# ESP32.net
KiCad netlist of a schematic drawn in Altium Designer
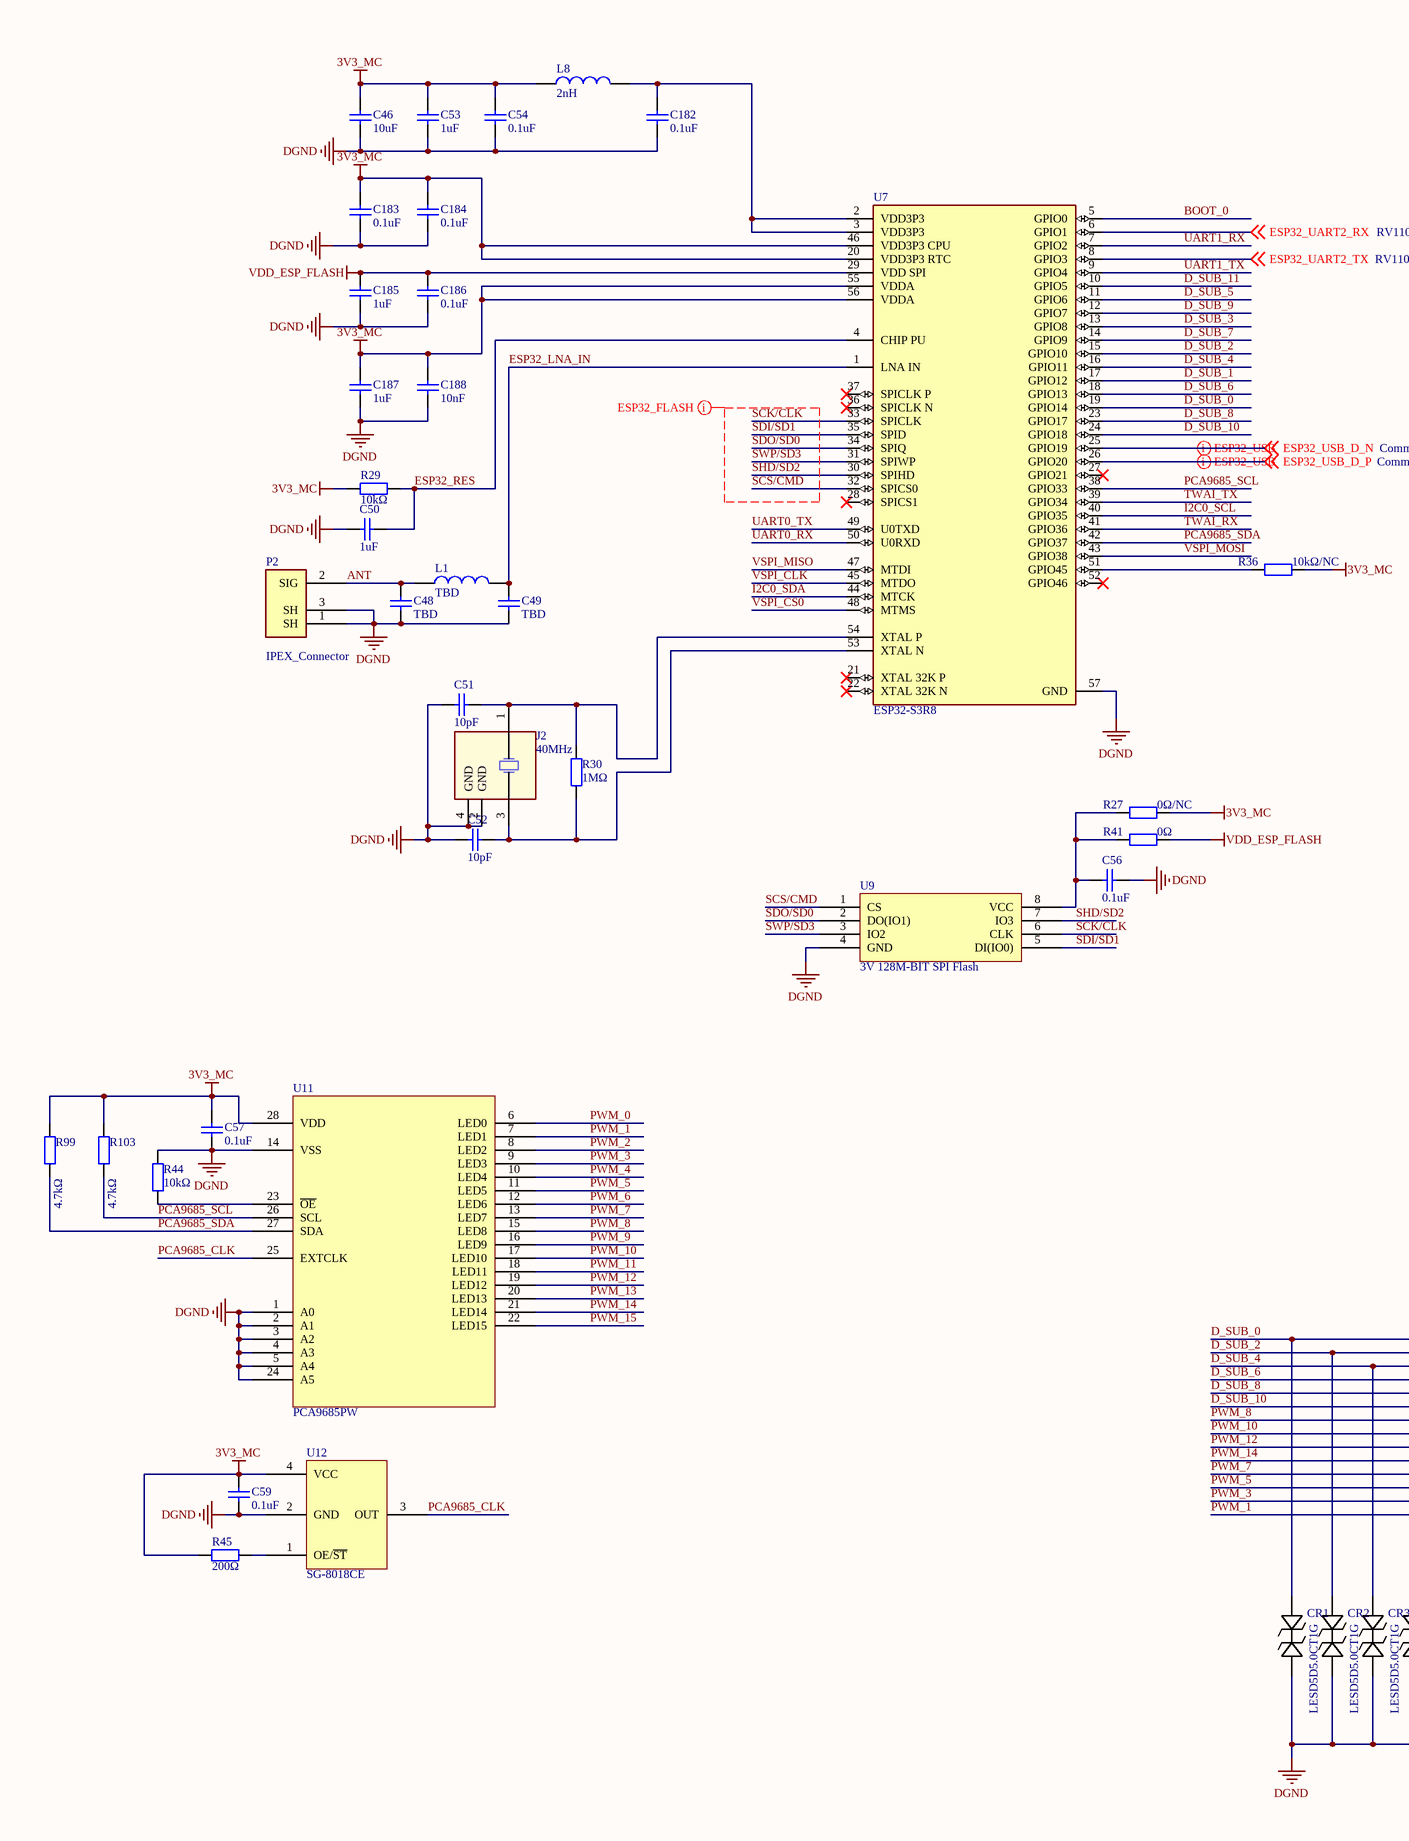
[diagram p0: ESP32.SchDoc, left]
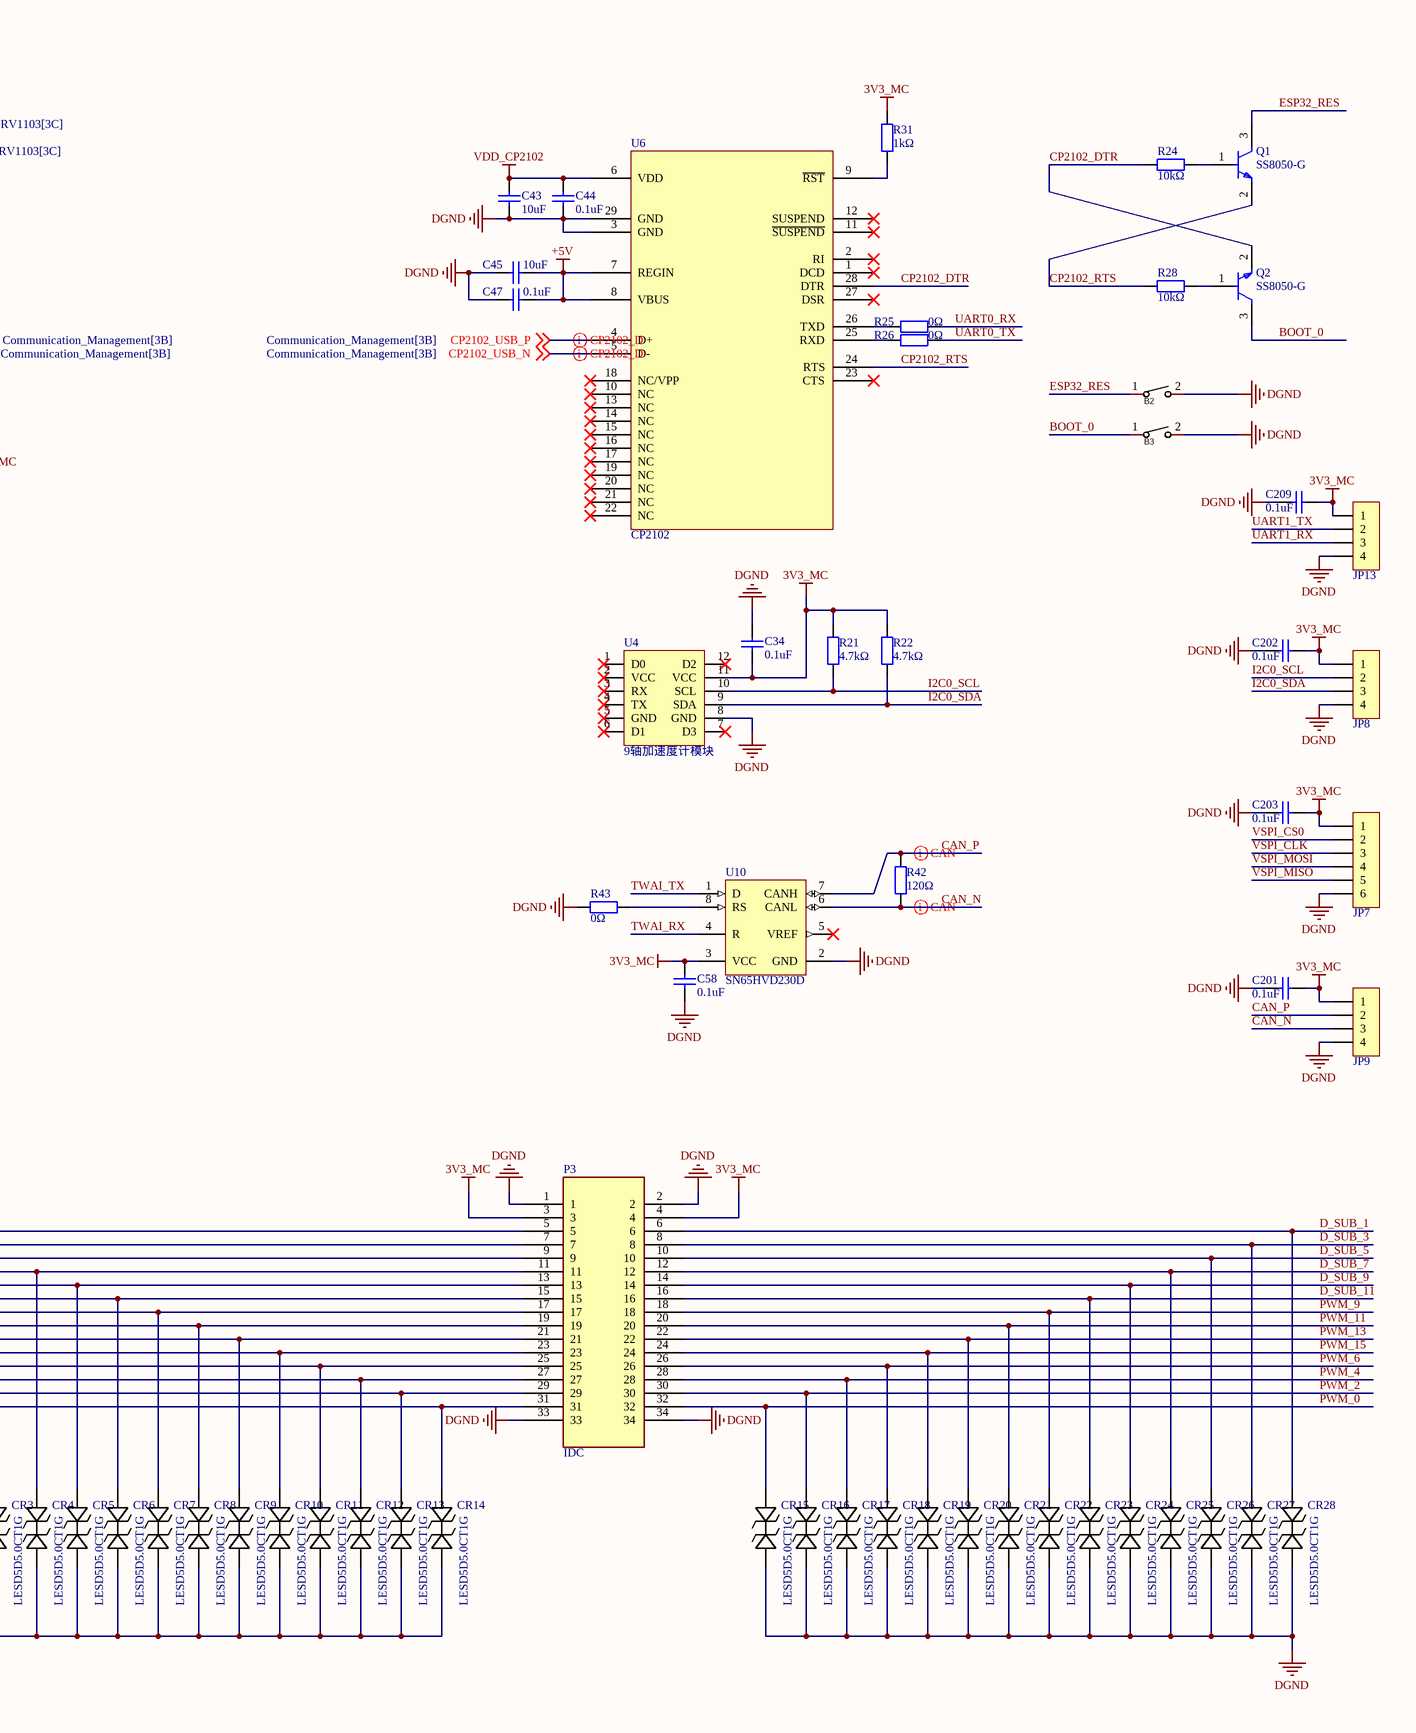
[diagram p1: ESP32.SchDoc, right]

(export (version "E")
  (design (tool "Eeschema 10.0.6"))
  (components
    (comp (ref "B2")
      (value "Bottom-2P-1Way")
      (footprint "SFerret:SW-SMD_L4.0-W2.9-LS5.0")
      (description "轻触按键")
      (fields (field (name "MANUFACTURER") "SHOU HAN(首韩)") (field (name "MANUFACTURER PART") "TS342A2P-WZ"))
      (libsource (lib "SFerret") (part "Bottom-2P-1Way"))
    )
    (comp (ref "B3")
      (value "Bottom-2P-1Way")
      (footprint "SW-SMD_L4.0-W2.9-LS5.0")
      (description "轻触按键")
      (fields (field (name "MANUFACTURER") "SHOU HAN(首韩)") (field (name "MANUFACTURER PART") "TS342A2P-WZ"))
      (libsource (lib "SFerret") (part "Bottom-2P-1Way"))
    )
    (comp (ref "C34")
      (value "0.1uF")
      (footprint "0603_C")
      (description "贴片电容")
      (libsource (lib "SFerret") (part "SMT_Cap"))
    )
    (comp (ref "C43")
      (value "10uF")
      (footprint "0603_C")
      (description "贴片电容")
      (libsource (lib "SFerret") (part "SMT_Cap"))
    )
    (comp (ref "C44")
      (value "0.1uF")
      (footprint "0603_C")
      (description "贴片电容")
      (libsource (lib "SFerret") (part "SMT_Cap"))
    )
    (comp (ref "C45")
      (value "10uF")
      (footprint "0603_C")
      (description "贴片电容")
      (libsource (lib "SFerret") (part "SMT_Cap"))
    )
    (comp (ref "C46")
      (value "10uF")
      (footprint "0603_C")
      (description "贴片电容")
      (libsource (lib "SFerret") (part "SMT_Cap"))
    )
    (comp (ref "C47")
      (value "0.1uF")
      (footprint "0603_C")
      (description "贴片电容")
      (libsource (lib "SFerret") (part "SMT_Cap"))
    )
    (comp (ref "C48")
      (value "TBD")
      (footprint "0402_C")
      (description "贴片电容")
      (libsource (lib "SFerret") (part "SMT_Cap"))
    )
    (comp (ref "C49")
      (value "TBD")
      (footprint "0402_C")
      (description "贴片电容")
      (libsource (lib "SFerret") (part "SMT_Cap"))
    )
    (comp (ref "C50")
      (value "1uF")
      (footprint "0402_C")
      (description "贴片电容")
      (libsource (lib "SFerret") (part "SMT_Cap"))
    )
    (comp (ref "C51")
      (value "10pF")
      (footprint "0402_C")
      (description "贴片电容")
      (libsource (lib "SFerret") (part "SMT_Cap"))
    )
    (comp (ref "C52")
      (value "10pF")
      (footprint "0402_C")
      (description "贴片电容")
      (libsource (lib "SFerret") (part "SMT_Cap"))
    )
    (comp (ref "C53")
      (value "1uF")
      (footprint "0603_C")
      (description "贴片电容")
      (libsource (lib "SFerret") (part "SMT_Cap"))
    )
    (comp (ref "C54")
      (value "0.1uF")
      (footprint "0402_C")
      (description "贴片电容")
      (libsource (lib "SFerret") (part "SMT_Cap"))
    )
    (comp (ref "C56")
      (value "0.1uF")
      (footprint "0603_C")
      (description "贴片电容")
      (libsource (lib "SFerret") (part "SMT_Cap"))
    )
    (comp (ref "C57")
      (value "0.1uF")
      (footprint "0603_C")
      (description "贴片电容")
      (libsource (lib "SFerret") (part "SMT_Cap"))
    )
    (comp (ref "C58")
      (value "0.1uF")
      (footprint "0603_C")
      (description "贴片电容")
      (libsource (lib "SFerret") (part "SMT_Cap"))
    )
    (comp (ref "C59")
      (value "0.1uF")
      (footprint "0603_C")
      (description "贴片电容")
      (libsource (lib "SFerret") (part "SMT_Cap"))
    )
    (comp (ref "C182")
      (value "0.1uF")
      (footprint "0402_C")
      (description "贴片电容")
      (libsource (lib "SFerret") (part "SMT_Cap"))
    )
    (comp (ref "C183")
      (value "0.1uF")
      (footprint "0402_C")
      (description "贴片电容")
      (libsource (lib "SFerret") (part "SMT_Cap"))
    )
    (comp (ref "C184")
      (value "0.1uF")
      (footprint "0402_C")
      (description "贴片电容")
      (libsource (lib "SFerret") (part "SMT_Cap"))
    )
    (comp (ref "C185")
      (value "1uF")
      (footprint "0402_C")
      (description "贴片电容")
      (libsource (lib "SFerret") (part "SMT_Cap"))
    )
    (comp (ref "C186")
      (value "0.1uF")
      (footprint "0402_C")
      (description "贴片电容")
      (libsource (lib "SFerret") (part "SMT_Cap"))
    )
    (comp (ref "C187")
      (value "1uF")
      (footprint "0402_C")
      (description "贴片电容")
      (libsource (lib "SFerret") (part "SMT_Cap"))
    )
    (comp (ref "C188")
      (value "10nF")
      (footprint "0402_C")
      (description "贴片电容")
      (libsource (lib "SFerret") (part "SMT_Cap"))
    )
    (comp (ref "C201")
      (value "0.1uF")
      (footprint "0603_C")
      (description "贴片电容")
      (libsource (lib "SFerret") (part "SMT_Cap"))
    )
    (comp (ref "C202")
      (value "0.1uF")
      (footprint "0603_C")
      (description "贴片电容")
      (libsource (lib "SFerret") (part "SMT_Cap"))
    )
    (comp (ref "C203")
      (value "0.1uF")
      (footprint "0603_C")
      (description "贴片电容")
      (libsource (lib "SFerret") (part "SMT_Cap"))
    )
    (comp (ref "C209")
      (value "0.1uF")
      (footprint "0603_C")
      (description "贴片电容")
      (libsource (lib "SFerret") (part "SMT_Cap"))
    )
    (comp (ref "CR1")
      (value "LESD5D5.0CT1G")
      (footprint "CR_5.0CT1G_UMW")
      (description "TVS")
      (libsource (lib "SFerret") (part "LESD5D5.0CT1G"))
    )
    (comp (ref "CR2")
      (value "LESD5D5.0CT1G")
      (footprint "CR_5.0CT1G_UMW")
      (description "TVS")
      (libsource (lib "SFerret") (part "LESD5D5.0CT1G"))
    )
    (comp (ref "CR3")
      (value "LESD5D5.0CT1G")
      (footprint "CR_5.0CT1G_UMW")
      (description "TVS")
      (libsource (lib "SFerret") (part "LESD5D5.0CT1G"))
    )
    (comp (ref "CR4")
      (value "LESD5D5.0CT1G")
      (footprint "CR_5.0CT1G_UMW")
      (description "TVS")
      (libsource (lib "SFerret") (part "LESD5D5.0CT1G"))
    )
    (comp (ref "CR5")
      (value "LESD5D5.0CT1G")
      (footprint "CR_5.0CT1G_UMW")
      (description "TVS")
      (libsource (lib "SFerret") (part "LESD5D5.0CT1G"))
    )
    (comp (ref "CR6")
      (value "LESD5D5.0CT1G")
      (footprint "CR_5.0CT1G_UMW")
      (description "TVS")
      (libsource (lib "SFerret") (part "LESD5D5.0CT1G"))
    )
    (comp (ref "CR7")
      (value "LESD5D5.0CT1G")
      (footprint "CR_5.0CT1G_UMW")
      (description "TVS")
      (libsource (lib "SFerret") (part "LESD5D5.0CT1G"))
    )
    (comp (ref "CR8")
      (value "LESD5D5.0CT1G")
      (footprint "CR_5.0CT1G_UMW")
      (description "TVS")
      (libsource (lib "SFerret") (part "LESD5D5.0CT1G"))
    )
    (comp (ref "CR9")
      (value "LESD5D5.0CT1G")
      (footprint "CR_5.0CT1G_UMW")
      (description "TVS")
      (libsource (lib "SFerret") (part "LESD5D5.0CT1G"))
    )
    (comp (ref "CR10")
      (value "LESD5D5.0CT1G")
      (footprint "CR_5.0CT1G_UMW")
      (description "TVS")
      (libsource (lib "SFerret") (part "LESD5D5.0CT1G"))
    )
    (comp (ref "CR11")
      (value "LESD5D5.0CT1G")
      (footprint "CR_5.0CT1G_UMW")
      (description "TVS")
      (libsource (lib "SFerret") (part "LESD5D5.0CT1G"))
    )
    (comp (ref "CR12")
      (value "LESD5D5.0CT1G")
      (footprint "CR_5.0CT1G_UMW")
      (description "TVS")
      (libsource (lib "SFerret") (part "LESD5D5.0CT1G"))
    )
    (comp (ref "CR13")
      (value "LESD5D5.0CT1G")
      (footprint "CR_5.0CT1G_UMW")
      (description "TVS")
      (libsource (lib "SFerret") (part "LESD5D5.0CT1G"))
    )
    (comp (ref "CR14")
      (value "LESD5D5.0CT1G")
      (footprint "CR_5.0CT1G_UMW")
      (description "TVS")
      (libsource (lib "SFerret") (part "LESD5D5.0CT1G"))
    )
    (comp (ref "CR15")
      (value "LESD5D5.0CT1G")
      (footprint "CR_5.0CT1G_UMW")
      (description "TVS")
      (libsource (lib "SFerret") (part "LESD5D5.0CT1G"))
    )
    (comp (ref "CR16")
      (value "LESD5D5.0CT1G")
      (footprint "CR_5.0CT1G_UMW")
      (description "TVS")
      (libsource (lib "SFerret") (part "LESD5D5.0CT1G"))
    )
    (comp (ref "CR17")
      (value "LESD5D5.0CT1G")
      (footprint "CR_5.0CT1G_UMW")
      (description "TVS")
      (libsource (lib "SFerret") (part "LESD5D5.0CT1G"))
    )
    (comp (ref "CR18")
      (value "LESD5D5.0CT1G")
      (footprint "CR_5.0CT1G_UMW")
      (description "TVS")
      (libsource (lib "SFerret") (part "LESD5D5.0CT1G"))
    )
    (comp (ref "CR19")
      (value "LESD5D5.0CT1G")
      (footprint "CR_5.0CT1G_UMW")
      (description "TVS")
      (libsource (lib "SFerret") (part "LESD5D5.0CT1G"))
    )
    (comp (ref "CR20")
      (value "LESD5D5.0CT1G")
      (footprint "CR_5.0CT1G_UMW")
      (description "TVS")
      (libsource (lib "SFerret") (part "LESD5D5.0CT1G"))
    )
    (comp (ref "CR21")
      (value "LESD5D5.0CT1G")
      (footprint "CR_5.0CT1G_UMW")
      (description "TVS")
      (libsource (lib "SFerret") (part "LESD5D5.0CT1G"))
    )
    (comp (ref "CR22")
      (value "LESD5D5.0CT1G")
      (footprint "CR_5.0CT1G_UMW")
      (description "TVS")
      (libsource (lib "SFerret") (part "LESD5D5.0CT1G"))
    )
    (comp (ref "CR23")
      (value "LESD5D5.0CT1G")
      (footprint "CR_5.0CT1G_UMW")
      (description "TVS")
      (libsource (lib "SFerret") (part "LESD5D5.0CT1G"))
    )
    (comp (ref "CR24")
      (value "LESD5D5.0CT1G")
      (footprint "CR_5.0CT1G_UMW")
      (description "TVS")
      (libsource (lib "SFerret") (part "LESD5D5.0CT1G"))
    )
    (comp (ref "CR25")
      (value "LESD5D5.0CT1G")
      (footprint "CR_5.0CT1G_UMW")
      (description "TVS")
      (libsource (lib "SFerret") (part "LESD5D5.0CT1G"))
    )
    (comp (ref "CR26")
      (value "LESD5D5.0CT1G")
      (footprint "CR_5.0CT1G_UMW")
      (description "TVS")
      (libsource (lib "SFerret") (part "LESD5D5.0CT1G"))
    )
    (comp (ref "CR27")
      (value "LESD5D5.0CT1G")
      (footprint "CR_5.0CT1G_UMW")
      (description "TVS")
      (libsource (lib "SFerret") (part "LESD5D5.0CT1G"))
    )
    (comp (ref "CR28")
      (value "LESD5D5.0CT1G")
      (footprint "CR_5.0CT1G_UMW")
      (description "TVS")
      (libsource (lib "SFerret") (part "LESD5D5.0CT1G"))
    )
    (comp (ref "J2")
      (value "40MHz")
      (footprint "SMD-2520_4P")
      (libsource (lib "SFerret") (part "Oscillator_SMT_4P"))
    )
    (comp (ref "JP7")
      (value "HDR-1X6")
      (footprint "MX 1.25-LS-6P")
      (description "6P接插件")
      (libsource (lib "5.0 - 接插件-脚距1.25") (part "Header 6"))
    )
    (comp (ref "JP8")
      (value "HDR-1X4")
      (footprint "MX 1.25-LS-4P")
      (description "4P接插件")
      (libsource (lib "5.0 - 接插件-脚距1.25") (part "Header 4"))
    )
    (comp (ref "JP9")
      (value "HDR-1X4")
      (footprint "MX 1.25-LS-4P")
      (description "4P接插件")
      (libsource (lib "5.0 - 接插件-脚距1.25") (part "Header 4"))
    )
    (comp (ref "JP13")
      (value "HDR-1X4")
      (footprint "MX 1.25-LS-4P")
      (description "4P接插件")
      (libsource (lib "5.0 - 接插件-脚距1.25") (part "Header 4"))
    )
    (comp (ref "L1")
      (value "TBD")
      (footprint "0402_L")
      (description "贴片电感")
      (libsource (lib "SFerret") (part "SMT_Iud"))
    )
    (comp (ref "L8")
      (value "2nH")
      (footprint "0402_L")
      (description "贴片电感")
      (libsource (lib "SFerret") (part "SMT_Iud"))
    )
    (comp (ref "P2")
      (value "IPEX_Connector")
      (footprint "IPEX")
      (libsource (lib "SFerret") (part "IPEX_Connector"))
    )
    (comp (ref "P3")
      (value "IDC")
      (footprint "IDC2.54-LI-2x17P")
      (libsource (lib "SFerret") (part "IDC 2x17P"))
    )
    (comp (ref "Q1")
      (value "SS8050-G")
      (footprint "FP-SS8050-G-MFG")
      (description "NPN TRANSISTOR 1.5A 40V SOT-23 R")
      (libsource (lib "Altium Content Vault") (part "2a1388f82443b098dcd57d24ac7632d"))
    )
    (comp (ref "Q2")
      (value "SS8050-G")
      (footprint "FP-SS8050-G-MFG")
      (description "NPN TRANSISTOR 1.5A 40V SOT-23 R")
      (libsource (lib "Altium Content Vault") (part "2a1388f82443b098dcd57d24ac7632d"))
    )
    (comp (ref "R21")
      (value "4.7kΩ")
      (footprint "0603_R")
      (description "贴片电阻")
      (libsource (lib "") (part "SMT_Res_1"))
    )
    (comp (ref "R22")
      (value "4.7kΩ")
      (footprint "0603_R")
      (description "贴片电阻")
      (libsource (lib "") (part "SMT_Res_1"))
    )
    (comp (ref "R24")
      (value "10kΩ")
      (footprint "0603_R")
      (description "贴片电阻")
      (libsource (lib "") (part "SMT_Res_3"))
    )
    (comp (ref "R25")
      (value "0Ω")
      (footprint "0603_R")
      (description "贴片电阻")
      (libsource (lib "") (part "SMT_Res_3"))
    )
    (comp (ref "R26")
      (value "0Ω")
      (footprint "0603_R")
      (description "贴片电阻")
      (libsource (lib "") (part "SMT_Res_3"))
    )
    (comp (ref "R27")
      (value "0Ω/NC")
      (footprint "0402_R")
      (description "贴片电阻")
      (libsource (lib "") (part "SMT_Res_3"))
    )
    (comp (ref "R28")
      (value "10kΩ")
      (footprint "0603_R")
      (description "贴片电阻")
      (libsource (lib "") (part "SMT_Res_3"))
    )
    (comp (ref "R29")
      (value "10kΩ")
      (footprint "0402_R")
      (description "贴片电阻")
      (libsource (lib "") (part "SMT_Res_3"))
    )
    (comp (ref "R30")
      (value "1MΩ")
      (footprint "0402_R")
      (description "贴片电阻")
      (libsource (lib "SFerret") (part "SMT_Res"))
    )
    (comp (ref "R31")
      (value "1kΩ")
      (footprint "0603_R")
      (description "贴片电阻")
      (libsource (lib "") (part "SMT_Res_1"))
    )
    (comp (ref "R36")
      (value "10kΩ/NC")
      (footprint "0402_R")
      (description "贴片电阻")
      (libsource (lib "") (part "SMT_Res_3"))
    )
    (comp (ref "R41")
      (value "0Ω")
      (footprint "0402_R")
      (description "贴片电阻")
      (libsource (lib "") (part "SMT_Res_3"))
    )
    (comp (ref "R42")
      (value "120Ω")
      (footprint "0805_R")
      (description "贴片电阻")
      (libsource (lib "") (part "SMT_Res_1"))
    )
    (comp (ref "R43")
      (value "0Ω")
      (footprint "0603_R")
      (description "贴片电阻")
      (libsource (lib "") (part "SMT_Res_3"))
    )
    (comp (ref "R44")
      (value "10kΩ")
      (footprint "0603_R")
      (description "贴片电阻")
      (libsource (lib "") (part "SMT_Res_1"))
    )
    (comp (ref "R45")
      (value "200Ω")
      (footprint "0603_R")
      (description "贴片电阻")
      (libsource (lib "") (part "SMT_Res_2"))
    )
    (comp (ref "R99")
      (value "4.7kΩ")
      (footprint "0603_R")
      (description "贴片电阻")
      (libsource (lib "SFerret") (part "SMT_Res"))
    )
    (comp (ref "R103")
      (value "4.7kΩ")
      (footprint "0603_R")
      (description "贴片电阻")
      (libsource (lib "SFerret") (part "SMT_Res"))
    )
    (comp (ref "U4") (value "9轴加速度计模块") (footprint "9轴加速度计") (libsource (lib "集大电协1.5") (part "9轴加速度计")))
    (comp (ref "U6")
      (value "CP2102")
      (footprint "QFN50P500X500X100_HS-29N")
      (description "SINGLE-CHIP USB TO UART BRIDGE")
      (libsource (lib "SFerret") (part "CP2102"))
    )
    (comp (ref "U7")
      (value "ESP32-S3R8")
      (footprint "QFN40P700X700X90_HS-57M")
      (description "ESP32-S3R8 RF System")
      (libsource (lib "SFerret") (part "ESP32-S3R8"))
    )
    (comp (ref "U9")
      (value "3V 128M-BIT SPI Flash")
      (footprint "SOIC-8-Body 5.28x5.28mm")
      (libsource (lib "SFerret") (part "W25Q128JVPIQ"))
    )
    (comp (ref "U10")
      (value "SN65HVD230D")
      (footprint "D0008A_M")
      (description "CAN Bus Transceiver, 3.3 V, -40 to 85 degC, 8-Pin SOIC (D), Green (RoHS & no Sb/Br), Tube")
      (fields (field (name "GENERIC PART NUMBER") "SN65HVD230"))
      (libsource (lib "Altium Content Vault") (part "TI-SN65HVD230D-SOIC_D-8"))
    )
    (comp (ref "U11")
      (value "PCA9685PW")
      (footprint "SOP65P640X110-28N")
      (description "16-Channel, 12-bit PWM Fm+ I²C-Bus LED Driver")
      (libsource (lib "SFerret") (part "PCA9685PW"))
    )
    (comp (ref "U12")
      (value "SG-8018CE")
      (footprint "OSC-2520-4P")
      (description "CRYSTAL OSCILLATOR (Programmable)")
      (libsource (lib "SFerret") (part "SG-8018CG_50Mhz"))
    )
  )
  (nets
    (net (code "1") (name "+5V") (class "Default")
      (node (ref "C45") (pin "1") (pinfunction "1_1") (pintype "passive"))
      (node (ref "C47") (pin "1") (pinfunction "1_1") (pintype "passive"))
      (node (ref "U6") (pin "7") (pinfunction "REGIN_7") (pintype "passive"))
      (node (ref "U6") (pin "8") (pinfunction "VBUS_8") (pintype "passive"))
    )
    (net (code "2") (name "/ANT") (class "Default")
      (node (ref "C48") (pin "2") (pinfunction "2_2") (pintype "passive"))
      (node (ref "L1") (pin "1") (pinfunction "1_1") (pintype "passive"))
      (node (ref "P2") (pin "2") (pinfunction "SIG_2") (pintype "passive"))
    )
    (net (code "3") (name "/BOOT_0") (class "Default")
      (node (ref "B3") (pin "1") (pinfunction "1_1") (pintype "passive"))
      (node (ref "Q2") (pin "3") (pinfunction "C_3") (pintype "passive"))
      (node (ref "U7") (pin "5") (pinfunction "GPIO0_5") (pintype "bidirectional"))
    )
    (net (code "4") (name "/CAN_N") (class "Default")
      (node (ref "JP9") (pin "3") (pinfunction "3_3") (pintype "passive"))
      (node (ref "R42") (pin "1") (pinfunction "1_1") (pintype "passive"))
      (node (ref "U10") (pin "6") (pinfunction "CANL_6") (pintype "bidirectional"))
    )
    (net (code "5") (name "/CAN_P") (class "Default")
      (node (ref "JP9") (pin "2") (pinfunction "2_2") (pintype "passive"))
      (node (ref "R42") (pin "2") (pinfunction "2_2") (pintype "passive"))
      (node (ref "U10") (pin "7") (pinfunction "CANH_7") (pintype "bidirectional"))
    )
    (net (code "6") (name "/CP2102_DTR") (class "Default")
      (node (ref "Q2") (pin "2") (pinfunction "E_2") (pintype "passive"))
      (node (ref "R24") (pin "1") (pinfunction "1_1") (pintype "passive"))
      (node (ref "U6") (pin "28") (pinfunction "DTR_28") (pintype "passive"))
    )
    (net (code "7") (name "/CP2102_RTS") (class "Default")
      (node (ref "Q1") (pin "2") (pinfunction "E_2") (pintype "passive"))
      (node (ref "R28") (pin "1") (pinfunction "1_1") (pintype "passive"))
      (node (ref "U6") (pin "24") (pinfunction "RTS_24") (pintype "passive"))
    )
    (net (code "8") (name "/D_SUB_0") (class "Default")
      (node (ref "CR1") (pin "1") (pinfunction "1_1") (pintype "passive"))
      (node (ref "P3") (pin "5") (pinfunction "5_5") (pintype "passive"))
      (node (ref "U7") (pin "19") (pinfunction "GPIO14_19") (pintype "bidirectional"))
    )
    (net (code "9") (name "/D_SUB_1") (class "Default")
      (node (ref "CR28") (pin "1") (pinfunction "1_1") (pintype "passive"))
      (node (ref "P3") (pin "6") (pinfunction "6_6") (pintype "passive"))
      (node (ref "U7") (pin "17") (pinfunction "GPIO12_17") (pintype "bidirectional"))
    )
    (net (code "10") (name "/D_SUB_2") (class "Default")
      (node (ref "CR2") (pin "1") (pinfunction "1_1") (pintype "passive"))
      (node (ref "P3") (pin "7") (pinfunction "7_7") (pintype "passive"))
      (node (ref "U7") (pin "15") (pinfunction "GPIO10_15") (pintype "bidirectional"))
    )
    (net (code "11") (name "/D_SUB_3") (class "Default")
      (node (ref "CR27") (pin "1") (pinfunction "1_1") (pintype "passive"))
      (node (ref "P3") (pin "8") (pinfunction "8_8") (pintype "passive"))
      (node (ref "U7") (pin "13") (pinfunction "GPIO8_13") (pintype "bidirectional"))
    )
    (net (code "12") (name "/D_SUB_4") (class "Default")
      (node (ref "CR3") (pin "1") (pinfunction "1_1") (pintype "passive"))
      (node (ref "P3") (pin "9") (pinfunction "9_9") (pintype "passive"))
      (node (ref "U7") (pin "16") (pinfunction "GPIO11_16") (pintype "bidirectional"))
    )
    (net (code "13") (name "/D_SUB_5") (class "Default")
      (node (ref "CR26") (pin "1") (pinfunction "1_1") (pintype "passive"))
      (node (ref "P3") (pin "10") (pinfunction "10_10") (pintype "passive"))
      (node (ref "U7") (pin "11") (pinfunction "GPIO6_11") (pintype "bidirectional"))
    )
    (net (code "14") (name "/D_SUB_6") (class "Default")
      (node (ref "CR4") (pin "1") (pinfunction "1_1") (pintype "passive"))
      (node (ref "P3") (pin "11") (pinfunction "11_11") (pintype "passive"))
      (node (ref "U7") (pin "18") (pinfunction "GPIO13_18") (pintype "bidirectional"))
    )
    (net (code "15") (name "/D_SUB_7") (class "Default")
      (node (ref "CR25") (pin "1") (pinfunction "1_1") (pintype "passive"))
      (node (ref "P3") (pin "12") (pinfunction "12_12") (pintype "passive"))
      (node (ref "U7") (pin "14") (pinfunction "GPIO9_14") (pintype "bidirectional"))
    )
    (net (code "16") (name "/D_SUB_8") (class "Default")
      (node (ref "CR5") (pin "1") (pinfunction "1_1") (pintype "passive"))
      (node (ref "P3") (pin "13") (pinfunction "13_13") (pintype "passive"))
      (node (ref "U7") (pin "23") (pinfunction "GPIO17_23") (pintype "bidirectional"))
    )
    (net (code "17") (name "/D_SUB_9") (class "Default")
      (node (ref "CR24") (pin "1") (pinfunction "1_1") (pintype "passive"))
      (node (ref "P3") (pin "14") (pinfunction "14_14") (pintype "passive"))
      (node (ref "U7") (pin "12") (pinfunction "GPIO7_12") (pintype "bidirectional"))
    )
    (net (code "18") (name "/D_SUB_10") (class "Default")
      (node (ref "CR6") (pin "1") (pinfunction "1_1") (pintype "passive"))
      (node (ref "P3") (pin "15") (pinfunction "15_15") (pintype "passive"))
      (node (ref "U7") (pin "24") (pinfunction "GPIO18_24") (pintype "bidirectional"))
    )
    (net (code "19") (name "/D_SUB_11") (class "Default")
      (node (ref "CR23") (pin "1") (pinfunction "1_1") (pintype "passive"))
      (node (ref "P3") (pin "16") (pinfunction "16_16") (pintype "passive"))
      (node (ref "U7") (pin "10") (pinfunction "GPIO5_10") (pintype "bidirectional"))
    )
    (net (code "20") (name "/ESP32_LNA_IN") (class "Default")
      (node (ref "C49") (pin "2") (pinfunction "2_2") (pintype "passive"))
      (node (ref "L1") (pin "2") (pinfunction "2_2") (pintype "passive"))
      (node (ref "U7") (pin "1") (pinfunction "LNA_IN_1") (pintype "passive"))
    )
    (net (code "21") (name "/ESP32_RES") (class "Default")
      (node (ref "B2") (pin "1") (pinfunction "1_1") (pintype "passive"))
      (node (ref "C50") (pin "2") (pinfunction "2_2") (pintype "passive"))
      (node (ref "Q1") (pin "3") (pinfunction "C_3") (pintype "passive"))
      (node (ref "R29") (pin "2") (pinfunction "2_2") (pintype "passive"))
      (node (ref "U7") (pin "4") (pinfunction "CHIP_PU_4") (pintype "passive"))
    )
    (net (code "22") (name "/I2C0_SCL") (class "Default")
      (node (ref "JP8") (pin "2") (pinfunction "2_2") (pintype "passive"))
      (node (ref "R21") (pin "1") (pinfunction "1_1") (pintype "passive"))
      (node (ref "U4") (pin "10") (pinfunction "SCL_10") (pintype "passive"))
      (node (ref "U7") (pin "40") (pinfunction "GPIO35_40") (pintype "bidirectional"))
    )
    (net (code "23") (name "/I2C0_SDA") (class "Default")
      (node (ref "JP8") (pin "3") (pinfunction "3_3") (pintype "passive"))
      (node (ref "R22") (pin "1") (pinfunction "1_1") (pintype "passive"))
      (node (ref "U4") (pin "9") (pinfunction "SDA_9") (pintype "passive"))
      (node (ref "U7") (pin "44") (pinfunction "MTCK_44") (pintype "bidirectional"))
    )
    (net (code "24") (name "/PCA9685_CLK") (class "Default")
      (node (ref "U11") (pin "25") (pinfunction "EXTCLK_25") (pintype "passive"))
      (node (ref "U12") (pin "3") (pinfunction "OUT_3") (pintype "passive"))
    )
    (net (code "25") (name "/PCA9685_SCL") (class "Default")
      (node (ref "R103") (pin "2") (pinfunction "2_2") (pintype "passive"))
      (node (ref "U11") (pin "26") (pinfunction "SCL_26") (pintype "passive"))
      (node (ref "U7") (pin "38") (pinfunction "GPIO33_38") (pintype "bidirectional"))
    )
    (net (code "26") (name "/PCA9685_SDA") (class "Default")
      (node (ref "R99") (pin "2") (pinfunction "2_2") (pintype "passive"))
      (node (ref "U11") (pin "27") (pinfunction "SDA_27") (pintype "passive"))
      (node (ref "U7") (pin "42") (pinfunction "GPIO37_42") (pintype "bidirectional"))
    )
    (net (code "27") (name "/PWM_0") (class "Default")
      (node (ref "CR15") (pin "1") (pinfunction "1_1") (pintype "passive"))
      (node (ref "P3") (pin "32") (pinfunction "32_32") (pintype "passive"))
      (node (ref "U11") (pin "6") (pinfunction "LED0_6") (pintype "passive"))
    )
    (net (code "28") (name "/PWM_1") (class "Default")
      (node (ref "CR14") (pin "1") (pinfunction "1_1") (pintype "passive"))
      (node (ref "P3") (pin "31") (pinfunction "31_31") (pintype "passive"))
      (node (ref "U11") (pin "7") (pinfunction "LED1_7") (pintype "passive"))
    )
    (net (code "29") (name "/PWM_2") (class "Default")
      (node (ref "CR16") (pin "1") (pinfunction "1_1") (pintype "passive"))
      (node (ref "P3") (pin "30") (pinfunction "30_30") (pintype "passive"))
      (node (ref "U11") (pin "8") (pinfunction "LED2_8") (pintype "passive"))
    )
    (net (code "30") (name "/PWM_3") (class "Default")
      (node (ref "CR13") (pin "1") (pinfunction "1_1") (pintype "passive"))
      (node (ref "P3") (pin "29") (pinfunction "29_29") (pintype "passive"))
      (node (ref "U11") (pin "9") (pinfunction "LED3_9") (pintype "passive"))
    )
    (net (code "31") (name "/PWM_4") (class "Default")
      (node (ref "CR17") (pin "1") (pinfunction "1_1") (pintype "passive"))
      (node (ref "P3") (pin "28") (pinfunction "28_28") (pintype "passive"))
      (node (ref "U11") (pin "10") (pinfunction "LED4_10") (pintype "passive"))
    )
    (net (code "32") (name "/PWM_5") (class "Default")
      (node (ref "CR12") (pin "1") (pinfunction "1_1") (pintype "passive"))
      (node (ref "P3") (pin "27") (pinfunction "27_27") (pintype "passive"))
      (node (ref "U11") (pin "11") (pinfunction "LED5_11") (pintype "passive"))
    )
    (net (code "33") (name "/PWM_6") (class "Default")
      (node (ref "CR18") (pin "1") (pinfunction "1_1") (pintype "passive"))
      (node (ref "P3") (pin "26") (pinfunction "26_26") (pintype "passive"))
      (node (ref "U11") (pin "12") (pinfunction "LED6_12") (pintype "passive"))
    )
    (net (code "34") (name "/PWM_7") (class "Default")
      (node (ref "CR11") (pin "1") (pinfunction "1_1") (pintype "passive"))
      (node (ref "P3") (pin "25") (pinfunction "25_25") (pintype "passive"))
      (node (ref "U11") (pin "13") (pinfunction "LED7_13") (pintype "passive"))
    )
    (net (code "35") (name "/PWM_8") (class "Default")
      (node (ref "CR7") (pin "1") (pinfunction "1_1") (pintype "passive"))
      (node (ref "P3") (pin "17") (pinfunction "17_17") (pintype "passive"))
      (node (ref "U11") (pin "15") (pinfunction "LED8_15") (pintype "passive"))
    )
    (net (code "36") (name "/PWM_9") (class "Default")
      (node (ref "CR22") (pin "1") (pinfunction "1_1") (pintype "passive"))
      (node (ref "P3") (pin "18") (pinfunction "18_18") (pintype "passive"))
      (node (ref "U11") (pin "16") (pinfunction "LED9_16") (pintype "passive"))
    )
    (net (code "37") (name "/PWM_10") (class "Default")
      (node (ref "CR8") (pin "1") (pinfunction "1_1") (pintype "passive"))
      (node (ref "P3") (pin "19") (pinfunction "19_19") (pintype "passive"))
      (node (ref "U11") (pin "17") (pinfunction "LED10_17") (pintype "passive"))
    )
    (net (code "38") (name "/PWM_11") (class "Default")
      (node (ref "CR21") (pin "1") (pinfunction "1_1") (pintype "passive"))
      (node (ref "P3") (pin "20") (pinfunction "20_20") (pintype "passive"))
      (node (ref "U11") (pin "18") (pinfunction "LED11_18") (pintype "passive"))
    )
    (net (code "39") (name "/PWM_12") (class "Default")
      (node (ref "CR9") (pin "1") (pinfunction "1_1") (pintype "passive"))
      (node (ref "P3") (pin "21") (pinfunction "21_21") (pintype "passive"))
      (node (ref "U11") (pin "19") (pinfunction "LED12_19") (pintype "passive"))
    )
    (net (code "40") (name "/PWM_13") (class "Default")
      (node (ref "CR20") (pin "1") (pinfunction "1_1") (pintype "passive"))
      (node (ref "P3") (pin "22") (pinfunction "22_22") (pintype "passive"))
      (node (ref "U11") (pin "20") (pinfunction "LED13_20") (pintype "passive"))
    )
    (net (code "41") (name "/PWM_14") (class "Default")
      (node (ref "CR10") (pin "1") (pinfunction "1_1") (pintype "passive"))
      (node (ref "P3") (pin "23") (pinfunction "23_23") (pintype "passive"))
      (node (ref "U11") (pin "21") (pinfunction "LED14_21") (pintype "passive"))
    )
    (net (code "42") (name "/PWM_15") (class "Default")
      (node (ref "CR19") (pin "1") (pinfunction "1_1") (pintype "passive"))
      (node (ref "P3") (pin "24") (pinfunction "24_24") (pintype "passive"))
      (node (ref "U11") (pin "22") (pinfunction "LED15_22") (pintype "passive"))
    )
    (net (code "43") (name "/SCK{slash}CLK") (class "Default")
      (node (ref "U7") (pin "33") (pinfunction "SPICLK_33") (pintype "bidirectional"))
      (node (ref "U9") (pin "6") (pinfunction "CLK_6") (pintype "passive"))
    )
    (net (code "44") (name "/SCS{slash}CMD") (class "Default")
      (node (ref "U7") (pin "32") (pinfunction "SPICS0_32") (pintype "bidirectional"))
      (node (ref "U9") (pin "1") (pinfunction "CS_1") (pintype "passive"))
    )
    (net (code "45") (name "/SDI{slash}SD1") (class "Default")
      (node (ref "U7") (pin "35") (pinfunction "SPID_35") (pintype "bidirectional"))
      (node (ref "U9") (pin "5") (pinfunction "DI(IO0)_5") (pintype "passive"))
    )
    (net (code "46") (name "/SDO{slash}SD0") (class "Default")
      (node (ref "U7") (pin "34") (pinfunction "SPIQ_34") (pintype "bidirectional"))
      (node (ref "U9") (pin "2") (pinfunction "DO(IO1)_2") (pintype "passive"))
    )
    (net (code "47") (name "/SHD{slash}SD2") (class "Default")
      (node (ref "U7") (pin "30") (pinfunction "SPIHD_30") (pintype "bidirectional"))
      (node (ref "U9") (pin "7") (pinfunction "IO3_7") (pintype "passive"))
    )
    (net (code "48") (name "/SWP{slash}SD3") (class "Default")
      (node (ref "U7") (pin "31") (pinfunction "SPIWP_31") (pintype "bidirectional"))
      (node (ref "U9") (pin "3") (pinfunction "IO2_3") (pintype "passive"))
    )
    (net (code "49") (name "/TWAI_RX") (class "Default")
      (node (ref "U10") (pin "4") (pinfunction "R_4") (pintype "passive"))
      (node (ref "U7") (pin "41") (pinfunction "GPIO36_41") (pintype "bidirectional"))
    )
    (net (code "50") (name "/TWAI_TX") (class "Default")
      (node (ref "U10") (pin "1") (pinfunction "D_1") (pintype "input"))
      (node (ref "U7") (pin "39") (pinfunction "GPIO34_39") (pintype "bidirectional"))
    )
    (net (code "51") (name "/UART0_RX") (class "Default")
      (node (ref "R25") (pin "2") (pinfunction "2_2") (pintype "passive"))
      (node (ref "U7") (pin "50") (pinfunction "U0RXD_50") (pintype "bidirectional"))
    )
    (net (code "52") (name "/UART0_TX") (class "Default")
      (node (ref "R26") (pin "2") (pinfunction "2_2") (pintype "passive"))
      (node (ref "U7") (pin "49") (pinfunction "U0TXD_49") (pintype "bidirectional"))
    )
    (net (code "53") (name "/UART1_RX") (class "Default")
      (node (ref "JP13") (pin "3") (pinfunction "3_3") (pintype "passive"))
      (node (ref "U7") (pin "7") (pinfunction "GPIO2_7") (pintype "bidirectional"))
    )
    (net (code "54") (name "/UART1_TX") (class "Default")
      (node (ref "JP13") (pin "2") (pinfunction "2_2") (pintype "passive"))
      (node (ref "U7") (pin "9") (pinfunction "GPIO4_9") (pintype "bidirectional"))
    )
    (net (code "55") (name "/VSPI_CLK") (class "Default")
      (node (ref "JP7") (pin "3") (pinfunction "3_3") (pintype "passive"))
      (node (ref "U7") (pin "45") (pinfunction "MTDO_45") (pintype "bidirectional"))
    )
    (net (code "56") (name "/VSPI_CS0") (class "Default")
      (node (ref "JP7") (pin "2") (pinfunction "2_2") (pintype "passive"))
      (node (ref "U7") (pin "48") (pinfunction "MTMS_48") (pintype "bidirectional"))
    )
    (net (code "57") (name "/VSPI_MISO") (class "Default")
      (node (ref "JP7") (pin "5") (pinfunction "5_5") (pintype "passive"))
      (node (ref "U7") (pin "47") (pinfunction "MTDI_47") (pintype "bidirectional"))
    )
    (net (code "58") (name "/VSPI_MOSI") (class "Default")
      (node (ref "JP7") (pin "4") (pinfunction "4_4") (pintype "passive"))
      (node (ref "U7") (pin "43") (pinfunction "GPIO38_43") (pintype "bidirectional"))
    )
    (net (code "59") (name "3V3_MC") (class "Default")
      (node (ref "C183") (pin "2") (pinfunction "2_2") (pintype "passive"))
      (node (ref "C184") (pin "2") (pinfunction "2_2") (pintype "passive"))
      (node (ref "C187") (pin "2") (pinfunction "2_2") (pintype "passive"))
      (node (ref "C188") (pin "2") (pinfunction "2_2") (pintype "passive"))
      (node (ref "C201") (pin "2") (pinfunction "2_2") (pintype "passive"))
      (node (ref "C202") (pin "2") (pinfunction "2_2") (pintype "passive"))
      (node (ref "C203") (pin "2") (pinfunction "2_2") (pintype "passive"))
      (node (ref "C209") (pin "2") (pinfunction "2_2") (pintype "passive"))
      (node (ref "C34") (pin "1") (pinfunction "1_1") (pintype "passive"))
      (node (ref "C46") (pin "2") (pinfunction "2_2") (pintype "passive"))
      (node (ref "C53") (pin "2") (pinfunction "2_2") (pintype "passive"))
      (node (ref "C54") (pin "2") (pinfunction "2_2") (pintype "passive"))
      (node (ref "C57") (pin "2") (pinfunction "2_2") (pintype "passive"))
      (node (ref "C58") (pin "2") (pinfunction "2_2") (pintype "passive"))
      (node (ref "C59") (pin "2") (pinfunction "2_2") (pintype "passive"))
      (node (ref "JP13") (pin "1") (pinfunction "1_1") (pintype "passive"))
      (node (ref "JP7") (pin "1") (pinfunction "1_1") (pintype "passive"))
      (node (ref "JP8") (pin "1") (pinfunction "1_1") (pintype "passive"))
      (node (ref "JP9") (pin "1") (pinfunction "1_1") (pintype "passive"))
      (node (ref "L8") (pin "1") (pinfunction "1_1") (pintype "passive"))
      (node (ref "P3") (pin "3") (pinfunction "3_3") (pintype "passive"))
      (node (ref "P3") (pin "4") (pinfunction "4_4") (pintype "passive"))
      (node (ref "R103") (pin "1") (pinfunction "1_1") (pintype "passive"))
      (node (ref "R21") (pin "2") (pinfunction "2_2") (pintype "passive"))
      (node (ref "R22") (pin "2") (pinfunction "2_2") (pintype "passive"))
      (node (ref "R27") (pin "2") (pinfunction "2_2") (pintype "passive"))
      (node (ref "R29") (pin "1") (pinfunction "1_1") (pintype "passive"))
      (node (ref "R31") (pin "2") (pinfunction "2_2") (pintype "passive"))
      (node (ref "R36") (pin "2") (pinfunction "2_2") (pintype "passive"))
      (node (ref "R45") (pin "2") (pinfunction "2_2") (pintype "passive"))
      (node (ref "R99") (pin "1") (pinfunction "1_1") (pintype "passive"))
      (node (ref "U10") (pin "3") (pinfunction "VCC_3") (pintype "power_in"))
      (node (ref "U11") (pin "28") (pinfunction "VDD_28") (pintype "passive"))
      (node (ref "U12") (pin "4") (pinfunction "VCC_4") (pintype "passive"))
      (node (ref "U4") (pin "11") (pinfunction "VCC_11") (pintype "passive"))
      (node (ref "U7") (pin "20") (pinfunction "VDD3P3_RTC_20") (pintype "power_in"))
      (node (ref "U7") (pin "46") (pinfunction "VDD3P3_CPU_46") (pintype "power_in"))
      (node (ref "U7") (pin "55") (pinfunction "VDDA_55") (pintype "power_in"))
      (node (ref "U7") (pin "56") (pinfunction "VDDA_56") (pintype "power_in"))
    )
    (net (code "60") (name "CP2102_USB_N") (class "Default")
      (node (ref "U6") (pin "5") (pinfunction "D-_5") (pintype "passive"))
    )
    (net (code "61") (name "CP2102_USB_P") (class "Default")
      (node (ref "U6") (pin "4") (pinfunction "D+_4") (pintype "passive"))
    )
    (net (code "62") (name "DGND") (class "Default")
      (node (ref "B2") (pin "2") (pinfunction "2_2") (pintype "passive"))
      (node (ref "B3") (pin "2") (pinfunction "2_2") (pintype "passive"))
      (node (ref "C182") (pin "1") (pinfunction "1_1") (pintype "passive"))
      (node (ref "C183") (pin "1") (pinfunction "1_1") (pintype "passive"))
      (node (ref "C184") (pin "1") (pinfunction "1_1") (pintype "passive"))
      (node (ref "C185") (pin "1") (pinfunction "1_1") (pintype "passive"))
      (node (ref "C186") (pin "1") (pinfunction "1_1") (pintype "passive"))
      (node (ref "C187") (pin "1") (pinfunction "1_1") (pintype "passive"))
      (node (ref "C188") (pin "1") (pinfunction "1_1") (pintype "passive"))
      (node (ref "C201") (pin "1") (pinfunction "1_1") (pintype "passive"))
      (node (ref "C202") (pin "1") (pinfunction "1_1") (pintype "passive"))
      (node (ref "C203") (pin "1") (pinfunction "1_1") (pintype "passive"))
      (node (ref "C209") (pin "1") (pinfunction "1_1") (pintype "passive"))
      (node (ref "C34") (pin "2") (pinfunction "2_2") (pintype "passive"))
      (node (ref "C43") (pin "2") (pinfunction "2_2") (pintype "passive"))
      (node (ref "C44") (pin "2") (pinfunction "2_2") (pintype "passive"))
      (node (ref "C45") (pin "2") (pinfunction "2_2") (pintype "passive"))
      (node (ref "C46") (pin "1") (pinfunction "1_1") (pintype "passive"))
      (node (ref "C47") (pin "2") (pinfunction "2_2") (pintype "passive"))
      (node (ref "C48") (pin "1") (pinfunction "1_1") (pintype "passive"))
      (node (ref "C49") (pin "1") (pinfunction "1_1") (pintype "passive"))
      (node (ref "C50") (pin "1") (pinfunction "1_1") (pintype "passive"))
      (node (ref "C51") (pin "1") (pinfunction "1_1") (pintype "passive"))
      (node (ref "C52") (pin "1") (pinfunction "1_1") (pintype "passive"))
      (node (ref "C53") (pin "1") (pinfunction "1_1") (pintype "passive"))
      (node (ref "C54") (pin "1") (pinfunction "1_1") (pintype "passive"))
      (node (ref "C56") (pin "2") (pinfunction "2_2") (pintype "passive"))
      (node (ref "C57") (pin "1") (pinfunction "1_1") (pintype "passive"))
      (node (ref "C58") (pin "1") (pinfunction "1_1") (pintype "passive"))
      (node (ref "C59") (pin "1") (pinfunction "1_1") (pintype "passive"))
      (node (ref "CR1") (pin "2") (pinfunction "2_2") (pintype "passive"))
      (node (ref "CR10") (pin "2") (pinfunction "2_2") (pintype "passive"))
      (node (ref "CR11") (pin "2") (pinfunction "2_2") (pintype "passive"))
      (node (ref "CR12") (pin "2") (pinfunction "2_2") (pintype "passive"))
      (node (ref "CR13") (pin "2") (pinfunction "2_2") (pintype "passive"))
      (node (ref "CR14") (pin "2") (pinfunction "2_2") (pintype "passive"))
      (node (ref "CR15") (pin "2") (pinfunction "2_2") (pintype "passive"))
      (node (ref "CR16") (pin "2") (pinfunction "2_2") (pintype "passive"))
      (node (ref "CR17") (pin "2") (pinfunction "2_2") (pintype "passive"))
      (node (ref "CR18") (pin "2") (pinfunction "2_2") (pintype "passive"))
      (node (ref "CR19") (pin "2") (pinfunction "2_2") (pintype "passive"))
      (node (ref "CR2") (pin "2") (pinfunction "2_2") (pintype "passive"))
      (node (ref "CR20") (pin "2") (pinfunction "2_2") (pintype "passive"))
      (node (ref "CR21") (pin "2") (pinfunction "2_2") (pintype "passive"))
      (node (ref "CR22") (pin "2") (pinfunction "2_2") (pintype "passive"))
      (node (ref "CR23") (pin "2") (pinfunction "2_2") (pintype "passive"))
      (node (ref "CR24") (pin "2") (pinfunction "2_2") (pintype "passive"))
      (node (ref "CR25") (pin "2") (pinfunction "2_2") (pintype "passive"))
      (node (ref "CR26") (pin "2") (pinfunction "2_2") (pintype "passive"))
      (node (ref "CR27") (pin "2") (pinfunction "2_2") (pintype "passive"))
      (node (ref "CR28") (pin "2") (pinfunction "2_2") (pintype "passive"))
      (node (ref "CR3") (pin "2") (pinfunction "2_2") (pintype "passive"))
      (node (ref "CR4") (pin "2") (pinfunction "2_2") (pintype "passive"))
      (node (ref "CR5") (pin "2") (pinfunction "2_2") (pintype "passive"))
      (node (ref "CR6") (pin "2") (pinfunction "2_2") (pintype "passive"))
      (node (ref "CR7") (pin "2") (pinfunction "2_2") (pintype "passive"))
      (node (ref "CR8") (pin "2") (pinfunction "2_2") (pintype "passive"))
      (node (ref "CR9") (pin "2") (pinfunction "2_2") (pintype "passive"))
      (node (ref "J2") (pin "2") (pinfunction "GND_2") (pintype "passive"))
      (node (ref "J2") (pin "4") (pinfunction "GND_4") (pintype "passive"))
      (node (ref "JP13") (pin "4") (pinfunction "4_4") (pintype "passive"))
      (node (ref "JP7") (pin "6") (pinfunction "6_6") (pintype "passive"))
      (node (ref "JP8") (pin "4") (pinfunction "4_4") (pintype "passive"))
      (node (ref "JP9") (pin "4") (pinfunction "4_4") (pintype "passive"))
      (node (ref "P2") (pin "1") (pinfunction "SH_1") (pintype "passive"))
      (node (ref "P2") (pin "3") (pinfunction "SH_3") (pintype "passive"))
      (node (ref "P3") (pin "1") (pinfunction "1_1") (pintype "passive"))
      (node (ref "P3") (pin "2") (pinfunction "2_2") (pintype "passive"))
      (node (ref "P3") (pin "33") (pinfunction "33_33") (pintype "passive"))
      (node (ref "P3") (pin "34") (pinfunction "34_34") (pintype "passive"))
      (node (ref "R43") (pin "1") (pinfunction "1_1") (pintype "passive"))
      (node (ref "R44") (pin "2") (pinfunction "2_2") (pintype "passive"))
      (node (ref "U10") (pin "2") (pinfunction "GND_2") (pintype "power_in"))
      (node (ref "U11") (pin "1") (pinfunction "A0_1") (pintype "passive"))
      (node (ref "U11") (pin "14") (pinfunction "VSS_14") (pintype "passive"))
      (node (ref "U11") (pin "2") (pinfunction "A1_2") (pintype "passive"))
      (node (ref "U11") (pin "24") (pinfunction "A5_24") (pintype "passive"))
      (node (ref "U11") (pin "3") (pinfunction "A2_3") (pintype "passive"))
      (node (ref "U11") (pin "4") (pinfunction "A3_4") (pintype "passive"))
      (node (ref "U11") (pin "5") (pinfunction "A4_5") (pintype "passive"))
      (node (ref "U12") (pin "2") (pinfunction "GND_2") (pintype "passive"))
      (node (ref "U4") (pin "8") (pinfunction "GND_8") (pintype "passive"))
      (node (ref "U6") (pin "29") (pinfunction "GND_29") (pintype "passive"))
      (node (ref "U6") (pin "3") (pinfunction "GND_3") (pintype "passive"))
      (node (ref "U7") (pin "57") (pinfunction "GND_57") (pintype "power_in"))
      (node (ref "U9") (pin "4") (pinfunction "GND_4") (pintype "passive"))
    )
    (net (code "63") (name "ESP32_UART2_RX") (class "Default")
      (node (ref "U7") (pin "6") (pinfunction "GPIO1_6") (pintype "bidirectional"))
    )
    (net (code "64") (name "ESP32_UART2_TX") (class "Default")
      (node (ref "U7") (pin "8") (pinfunction "GPIO3_8") (pintype "bidirectional"))
    )
    (net (code "65") (name "ESP32_USB_D_N") (class "Default")
      (node (ref "U7") (pin "25") (pinfunction "GPIO19_25") (pintype "bidirectional"))
    )
    (net (code "66") (name "ESP32_USB_D_P") (class "Default")
      (node (ref "U7") (pin "26") (pinfunction "GPIO20_26") (pintype "bidirectional"))
    )
    (net (code "67") (name "Net-(C182-Pad2)") (class "Default")
      (node (ref "C182") (pin "2") (pinfunction "2_2") (pintype "passive"))
      (node (ref "L8") (pin "2") (pinfunction "2_2") (pintype "passive"))
      (node (ref "U7") (pin "2") (pinfunction "VDD3P3_2") (pintype "power_in"))
      (node (ref "U7") (pin "3") (pinfunction "VDD3P3_3") (pintype "power_in"))
    )
    (net (code "68") (name "Net-(J2-OSC1)") (class "Default")
      (node (ref "C51") (pin "2") (pinfunction "2_2") (pintype "passive"))
      (node (ref "J2") (pin "1") (pinfunction "OSC1_1") (pintype "passive"))
      (node (ref "R30") (pin "1") (pinfunction "1_1") (pintype "passive"))
      (node (ref "U7") (pin "54") (pinfunction "XTAL_P_54") (pintype "passive"))
    )
    (net (code "69") (name "Net-(J2-OSC2)") (class "Default")
      (node (ref "C52") (pin "2") (pinfunction "2_2") (pintype "passive"))
      (node (ref "J2") (pin "3") (pinfunction "OSC2_3") (pintype "passive"))
      (node (ref "R30") (pin "2") (pinfunction "2_2") (pintype "passive"))
      (node (ref "U7") (pin "53") (pinfunction "XTAL_N_53") (pintype "passive"))
    )
    (net (code "70") (name "Net-(Q1-B)") (class "Default")
      (node (ref "Q1") (pin "1") (pinfunction "B_1") (pintype "passive"))
      (node (ref "R24") (pin "2") (pinfunction "2_2") (pintype "passive"))
    )
    (net (code "71") (name "Net-(Q2-B)") (class "Default")
      (node (ref "Q2") (pin "1") (pinfunction "B_1") (pintype "passive"))
      (node (ref "R28") (pin "2") (pinfunction "2_2") (pintype "passive"))
    )
    (net (code "72") (name "Net-(U6-RXD)") (class "Default")
      (node (ref "R26") (pin "1") (pinfunction "1_1") (pintype "passive"))
      (node (ref "U6") (pin "25") (pinfunction "RXD_25") (pintype "passive"))
    )
    (net (code "73") (name "Net-(U6-TXD)") (class "Default")
      (node (ref "R25") (pin "1") (pinfunction "1_1") (pintype "passive"))
      (node (ref "U6") (pin "26") (pinfunction "TXD_26") (pintype "passive"))
    )
    (net (code "74") (name "Net-(U6-~{RST})") (class "Default")
      (node (ref "R31") (pin "1") (pinfunction "1_1") (pintype "passive"))
      (node (ref "U6") (pin "9") (pinfunction "~{RST}_9") (pintype "passive"))
    )
    (net (code "75") (name "Net-(U7-GPIO45)") (class "Default")
      (node (ref "R36") (pin "1") (pinfunction "1_1") (pintype "passive"))
      (node (ref "U7") (pin "51") (pinfunction "GPIO45_51") (pintype "bidirectional"))
    )
    (net (code "76") (name "Net-(U9-VCC)") (class "Default")
      (node (ref "C56") (pin "1") (pinfunction "1_1") (pintype "passive"))
      (node (ref "R27") (pin "1") (pinfunction "1_1") (pintype "passive"))
      (node (ref "R41") (pin "1") (pinfunction "1_1") (pintype "passive"))
      (node (ref "U9") (pin "8") (pinfunction "VCC_8") (pintype "passive"))
    )
    (net (code "77") (name "Net-(U10-RS)") (class "Default")
      (node (ref "R43") (pin "2") (pinfunction "2_2") (pintype "passive"))
      (node (ref "U10") (pin "8") (pinfunction "RS_8") (pintype "input"))
    )
    (net (code "78") (name "Net-(U11-~{OE})") (class "Default")
      (node (ref "R44") (pin "1") (pinfunction "1_1") (pintype "passive"))
      (node (ref "U11") (pin "23") (pinfunction "~{OE}_23") (pintype "passive"))
    )
    (net (code "79") (name "Net-(U12-OE{slash}~{ST})") (class "Default")
      (node (ref "R45") (pin "1") (pinfunction "1_1") (pintype "passive"))
      (node (ref "U12") (pin "1") (pinfunction "OE/~{ST}_1") (pintype "passive"))
    )
    (net (code "80") (name "VDD_CP2102") (class "Default")
      (node (ref "C43") (pin "1") (pinfunction "1_1") (pintype "passive"))
      (node (ref "C44") (pin "1") (pinfunction "1_1") (pintype "passive"))
      (node (ref "U6") (pin "6") (pinfunction "VDD_6") (pintype "passive"))
    )
    (net (code "81") (name "VDD_ESP_FLASH") (class "Default")
      (node (ref "C185") (pin "2") (pinfunction "2_2") (pintype "passive"))
      (node (ref "C186") (pin "2") (pinfunction "2_2") (pintype "passive"))
      (node (ref "R41") (pin "2") (pinfunction "2_2") (pintype "passive"))
      (node (ref "U7") (pin "29") (pinfunction "VDD_SPI_29") (pintype "power_in"))
    )
    (net (code "82") (name "unconnected-(U4-D0-Pad1)") (class "Default")
      (node (ref "U4") (pin "1") (pinfunction "D0_1") (pintype "passive+no_connect"))
    )
    (net (code "83") (name "unconnected-(U4-D1-Pad6)") (class "Default")
      (node (ref "U4") (pin "6") (pinfunction "D1_6") (pintype "passive+no_connect"))
    )
    (net (code "84") (name "unconnected-(U4-D2-Pad12)") (class "Default")
      (node (ref "U4") (pin "12") (pinfunction "D2_12") (pintype "passive+no_connect"))
    )
    (net (code "85") (name "unconnected-(U4-D3-Pad7)") (class "Default")
      (node (ref "U4") (pin "7") (pinfunction "D3_7") (pintype "passive+no_connect"))
    )
    (net (code "86") (name "unconnected-(U4-GND-Pad5)") (class "Default")
      (node (ref "U4") (pin "5") (pinfunction "GND_5") (pintype "passive+no_connect"))
    )
    (net (code "87") (name "unconnected-(U4-RX-Pad3)") (class "Default")
      (node (ref "U4") (pin "3") (pinfunction "RX_3") (pintype "passive+no_connect"))
    )
    (net (code "88") (name "unconnected-(U4-TX-Pad4)") (class "Default")
      (node (ref "U4") (pin "4") (pinfunction "TX_4") (pintype "passive+no_connect"))
    )
    (net (code "89") (name "unconnected-(U4-VCC-Pad2)") (class "Default")
      (node (ref "U4") (pin "2") (pinfunction "VCC_2") (pintype "passive+no_connect"))
    )
    (net (code "90") (name "unconnected-(U6-CTS-Pad23)") (class "Default")
      (node (ref "U6") (pin "23") (pinfunction "CTS_23") (pintype "passive+no_connect"))
    )
    (net (code "91") (name "unconnected-(U6-DCD-Pad1)") (class "Default")
      (node (ref "U6") (pin "1") (pinfunction "DCD_1") (pintype "passive+no_connect"))
    )
    (net (code "92") (name "unconnected-(U6-DSR-Pad27)") (class "Default")
      (node (ref "U6") (pin "27") (pinfunction "DSR_27") (pintype "passive+no_connect"))
    )
    (net (code "93") (name "unconnected-(U6-NC-Pad10)") (class "Default")
      (node (ref "U6") (pin "10") (pinfunction "NC_10") (pintype "passive+no_connect"))
    )
    (net (code "94") (name "unconnected-(U6-NC-Pad13)") (class "Default")
      (node (ref "U6") (pin "13") (pinfunction "NC_13") (pintype "passive+no_connect"))
    )
    (net (code "95") (name "unconnected-(U6-NC-Pad14)") (class "Default")
      (node (ref "U6") (pin "14") (pinfunction "NC_14") (pintype "passive+no_connect"))
    )
    (net (code "96") (name "unconnected-(U6-NC-Pad15)") (class "Default")
      (node (ref "U6") (pin "15") (pinfunction "NC_15") (pintype "passive+no_connect"))
    )
    (net (code "97") (name "unconnected-(U6-NC-Pad16)") (class "Default")
      (node (ref "U6") (pin "16") (pinfunction "NC_16") (pintype "passive+no_connect"))
    )
    (net (code "98") (name "unconnected-(U6-NC-Pad17)") (class "Default")
      (node (ref "U6") (pin "17") (pinfunction "NC_17") (pintype "passive+no_connect"))
    )
    (net (code "99") (name "unconnected-(U6-NC-Pad19)") (class "Default")
      (node (ref "U6") (pin "19") (pinfunction "NC_19") (pintype "passive+no_connect"))
    )
    (net (code "100") (name "unconnected-(U6-NC-Pad20)") (class "Default")
      (node (ref "U6") (pin "20") (pinfunction "NC_20") (pintype "passive+no_connect"))
    )
    (net (code "101") (name "unconnected-(U6-NC-Pad21)") (class "Default")
      (node (ref "U6") (pin "21") (pinfunction "NC_21") (pintype "passive+no_connect"))
    )
    (net (code "102") (name "unconnected-(U6-NC-Pad22)") (class "Default")
      (node (ref "U6") (pin "22") (pinfunction "NC_22") (pintype "passive+no_connect"))
    )
    (net (code "103") (name "unconnected-(U6-NC{slash}VPP-Pad18)") (class "Default")
      (node (ref "U6") (pin "18") (pinfunction "NC/VPP_18") (pintype "passive+no_connect"))
    )
    (net (code "104") (name "unconnected-(U6-RI-Pad2)") (class "Default")
      (node (ref "U6") (pin "2") (pinfunction "RI_2") (pintype "passive+no_connect"))
    )
    (net (code "105") (name "unconnected-(U6-SUSPEND-Pad12)") (class "Default")
      (node (ref "U6") (pin "12") (pinfunction "SUSPEND_12") (pintype "passive+no_connect"))
    )
    (net (code "106") (name "unconnected-(U6-~{SUSPEND}-Pad11)") (class "Default")
      (node (ref "U6") (pin "11") (pinfunction "~{SUSPEND}_11") (pintype "passive+no_connect"))
    )
    (net (code "107") (name "unconnected-(U7-GPIO21-Pad27)") (class "Default")
      (node (ref "U7") (pin "27") (pinfunction "GPIO21_27") (pintype "bidirectional+no_connect"))
    )
    (net (code "108") (name "unconnected-(U7-GPIO46-Pad52)") (class "Default")
      (node (ref "U7") (pin "52") (pinfunction "GPIO46_52") (pintype "bidirectional+no_connect"))
    )
    (net (code "109") (name "unconnected-(U7-SPICLK_N-Pad36)") (class "Default")
      (node (ref "U7") (pin "36") (pinfunction "SPICLK_N_36") (pintype "bidirectional+no_connect"))
    )
    (net (code "110") (name "unconnected-(U7-SPICLK_P-Pad37)") (class "Default")
      (node (ref "U7") (pin "37") (pinfunction "SPICLK_P_37") (pintype "bidirectional+no_connect"))
    )
    (net (code "111") (name "unconnected-(U7-SPICS1-Pad28)") (class "Default")
      (node (ref "U7") (pin "28") (pinfunction "SPICS1_28") (pintype "bidirectional+no_connect"))
    )
    (net (code "112") (name "unconnected-(U7-XTAL_32K_N-Pad22)") (class "Default")
      (node (ref "U7") (pin "22") (pinfunction "XTAL_32K_N_22") (pintype "bidirectional+no_connect"))
    )
    (net (code "113") (name "unconnected-(U7-XTAL_32K_P-Pad21)") (class "Default")
      (node (ref "U7") (pin "21") (pinfunction "XTAL_32K_P_21") (pintype "bidirectional+no_connect"))
    )
    (net (code "114") (name "unconnected-(U10-VREF-Pad5)") (class "Default")
      (node (ref "U10") (pin "5") (pinfunction "VREF_5") (pintype "output+no_connect"))
    )
  )
)
